# PDB.net
KiCad netlist of a schematic drawn in Altium Designer
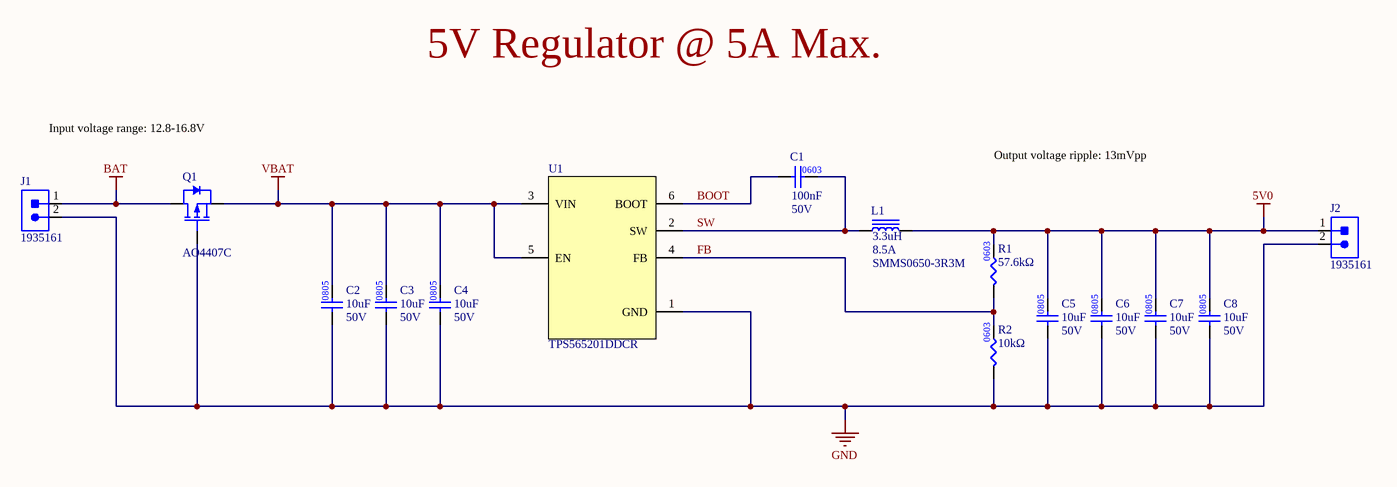
[diagram p0: PDB.SchDoc]

(export (version "E")
  (design (tool "Eeschema 10.0.6"))
  (components
    (comp (ref "C1")
      (value "100nF")
      (footprint "CAP0603")
      (description "CAP CER 100NF 50V X7R 0603")
      (fields
        (field (name "TOLERANCE") "10%")
        (field (name "VOLTAGE") "50V")
        (field (name "LCSC PART #") "C129621")
      )
      (libsource (lib "PDB") (part "CAP_100nF_50V_0603"))
    )
    (comp (ref "C2")
      (value "10uF")
      (footprint "CAP0805")
      (description "CAP CER 10UF 50V X5R 0805")
      (fields
        (field (name "TOLERANCE") "10%")
        (field (name "VOLTAGE") "50V")
        (field (name "LCSC PART #") "C440198")
      )
      (libsource (lib "PDB") (part "CAP_10uF_50V_0805"))
    )
    (comp (ref "C3")
      (value "10uF")
      (footprint "CAP0805")
      (description "CAP CER 10UF 50V X5R 0805")
      (fields
        (field (name "TOLERANCE") "10%")
        (field (name "VOLTAGE") "50V")
        (field (name "LCSC PART #") "C440198")
      )
      (libsource (lib "PDB") (part "CAP_10uF_50V_0805"))
    )
    (comp (ref "C4")
      (value "10uF")
      (footprint "CAP0805")
      (description "CAP CER 10UF 50V X5R 0805")
      (fields
        (field (name "TOLERANCE") "10%")
        (field (name "VOLTAGE") "50V")
        (field (name "LCSC PART #") "C440198")
      )
      (libsource (lib "PDB") (part "CAP_10uF_50V_0805"))
    )
    (comp (ref "C5")
      (value "10uF")
      (footprint "CAP0805")
      (description "CAP CER 10UF 50V X5R 0805")
      (fields
        (field (name "TOLERANCE") "10%")
        (field (name "VOLTAGE") "50V")
        (field (name "LCSC PART #") "C440198")
      )
      (libsource (lib "PDB") (part "CAP_10uF_50V_0805"))
    )
    (comp (ref "C6")
      (value "10uF")
      (footprint "CAP0805")
      (description "CAP CER 10UF 50V X5R 0805")
      (fields
        (field (name "TOLERANCE") "10%")
        (field (name "VOLTAGE") "50V")
        (field (name "LCSC PART #") "C440198")
      )
      (libsource (lib "PDB") (part "CAP_10uF_50V_0805"))
    )
    (comp (ref "C7")
      (value "10uF")
      (footprint "CAP0805")
      (description "CAP CER 10UF 50V X5R 0805")
      (fields
        (field (name "TOLERANCE") "10%")
        (field (name "VOLTAGE") "50V")
        (field (name "LCSC PART #") "C440198")
      )
      (libsource (lib "PDB") (part "CAP_10uF_50V_0805"))
    )
    (comp (ref "C8")
      (value "10uF")
      (footprint "CAP0805")
      (description "CAP CER 10UF 50V X5R 0805")
      (fields
        (field (name "TOLERANCE") "10%")
        (field (name "VOLTAGE") "50V")
        (field (name "LCSC PART #") "C440198")
      )
      (libsource (lib "PDB") (part "CAP_10uF_50V_0805"))
    )
    (comp (ref "J1")
      (value "CON_2POS_SCREW_TERM")
      (footprint "1935161")
      (description "TERM BLK 2POS SIDE ENTRY 5MM")
      (fields (field (name "MANUFACTURER PART NUMBER 1") "1935161"))
      (libsource (lib "") (part "CON_2POS_SCREW_TERM_1"))
    )
    (comp (ref "J2")
      (value "CON_2POS_SCREW_TERM")
      (footprint "1935161")
      (description "TERM BLK 2POS SIDE ENTRY 5MM")
      (fields (field (name "MANUFACTURER PART NUMBER 1") "1935161"))
      (libsource (lib "PDB") (part "CON_2POS_SCREW_TERM"))
    )
    (comp (ref "L1")
      (value "3.3uH")
      (footprint "SMMS0650-3R3M")
      (description "IND 3.3UH 8.5A 22M OHM")
      (fields
        (field (name "TOLERANCE") "20%")
        (field (name "CURRENT RATING") "8.5A")
        (field (name "MANUFACTURER PART NUMBER 1") "SMMS0650-3R3M")
        (field (name "LCSC PART #") "C149581")
      )
      (libsource (lib "PDB") (part "IND_3.3uH_8.5A"))
    )
    (comp (ref "Q1")
      (value "PMOS_30V_14A")
      (footprint "SO-8_PMOS_AO4407C")
      (description "MOSFET P-CH 30V 14A SO-8")
      (fields (field (name "MANUFACTURER PART NUMBER 1") "AO4407C") (field (name "LCSC PART #") "C469397"))
      (libsource (lib "PDB") (part "PMOS_30V_14A"))
    )
    (comp (ref "R1")
      (value "57.6kΩ")
      (footprint "RES0603")
      (description "RES 57.6K OHM 1% 1/10W 0603")
      (fields (field (name "TOLERANCE") "1%") (field (name "LCSC PART #") "C23082"))
      (libsource (lib "PDB") (part "RES_57.6kΩ_0603_1%"))
    )
    (comp (ref "R2")
      (value "10kΩ")
      (footprint "RES0603")
      (description "RES 10K OHM 1% 1/10W 0603")
      (fields (field (name "TOLERANCE") "1%") (field (name "LCSC PART #") "C25804"))
      (libsource (lib "PDB") (part "RES_10kΩ_0603_1%"))
    )
    (comp (ref "U1")
      (value "TPS565201DDCR")
      (footprint "TPS565201DDCR")
      (description "IC REG BUCK ADJ 5A TSOT23-6")
      (fields
        (field (name "MANUFACTURER") "Texas Instruments")
        (field (name "MANUFACTURER PART NUMBER") "TPS565201DDCR")
        (field (name "LCSC PART #") "C327676")
      )
      (libsource (lib "PDB") (part "TPS565201DDCR"))
    )
  )
  (nets
    (net (code "1") (name "/BOOT") (class "Default")
      (node (ref "C1") (pin "1") (pinfunction "1_1") (pintype "passive"))
      (node (ref "U1") (pin "6") (pinfunction "BOOT_6") (pintype "passive"))
    )
    (net (code "2") (name "/FB") (class "Default")
      (node (ref "R1") (pin "1") (pinfunction "1_1") (pintype "passive"))
      (node (ref "R2") (pin "2") (pinfunction "2_2") (pintype "passive"))
      (node (ref "U1") (pin "4") (pinfunction "FB_4") (pintype "passive"))
    )
    (net (code "3") (name "/SW") (class "Default")
      (node (ref "C1") (pin "2") (pinfunction "2_2") (pintype "passive"))
      (node (ref "L1") (pin "1") (pinfunction "1_1") (pintype "passive"))
      (node (ref "U1") (pin "2") (pinfunction "SW_2") (pintype "passive"))
    )
    (net (code "4") (name "5V0") (class "Default")
      (node (ref "C5") (pin "2") (pinfunction "2_2") (pintype "passive"))
      (node (ref "C6") (pin "2") (pinfunction "2_2") (pintype "passive"))
      (node (ref "C7") (pin "2") (pinfunction "2_2") (pintype "passive"))
      (node (ref "C8") (pin "2") (pinfunction "2_2") (pintype "passive"))
      (node (ref "J2") (pin "1") (pinfunction "1_1") (pintype "passive"))
      (node (ref "L1") (pin "2") (pinfunction "2_2") (pintype "passive"))
      (node (ref "R1") (pin "2") (pinfunction "2_2") (pintype "passive"))
    )
    (net (code "5") (name "BAT") (class "Default")
      (node (ref "J1") (pin "1") (pinfunction "1_1") (pintype "passive"))
      (node (ref "Q1") (pin "3") (pinfunction "Drain_3") (pintype "passive"))
    )
    (net (code "6") (name "GND") (class "Default")
      (node (ref "C2") (pin "1") (pinfunction "1_1") (pintype "passive"))
      (node (ref "C3") (pin "1") (pinfunction "1_1") (pintype "passive"))
      (node (ref "C4") (pin "1") (pinfunction "1_1") (pintype "passive"))
      (node (ref "C5") (pin "1") (pinfunction "1_1") (pintype "passive"))
      (node (ref "C6") (pin "1") (pinfunction "1_1") (pintype "passive"))
      (node (ref "C7") (pin "1") (pinfunction "1_1") (pintype "passive"))
      (node (ref "C8") (pin "1") (pinfunction "1_1") (pintype "passive"))
      (node (ref "J1") (pin "2") (pinfunction "2_2") (pintype "passive"))
      (node (ref "J2") (pin "2") (pinfunction "2_2") (pintype "passive"))
      (node (ref "Q1") (pin "2") (pinfunction "Gate_2") (pintype "passive"))
      (node (ref "R2") (pin "1") (pinfunction "1_1") (pintype "passive"))
      (node (ref "U1") (pin "1") (pinfunction "GND_1") (pintype "passive"))
    )
    (net (code "7") (name "VBAT") (class "Default")
      (node (ref "C2") (pin "2") (pinfunction "2_2") (pintype "passive"))
      (node (ref "C3") (pin "2") (pinfunction "2_2") (pintype "passive"))
      (node (ref "C4") (pin "2") (pinfunction "2_2") (pintype "passive"))
      (node (ref "Q1") (pin "1") (pinfunction "Source_1") (pintype "passive"))
      (node (ref "U1") (pin "3") (pinfunction "VIN_3") (pintype "passive"))
      (node (ref "U1") (pin "5") (pinfunction "EN_5") (pintype "passive"))
    )
  )
)
